# Power.net
KiCad netlist of a schematic drawn in Altium Designer
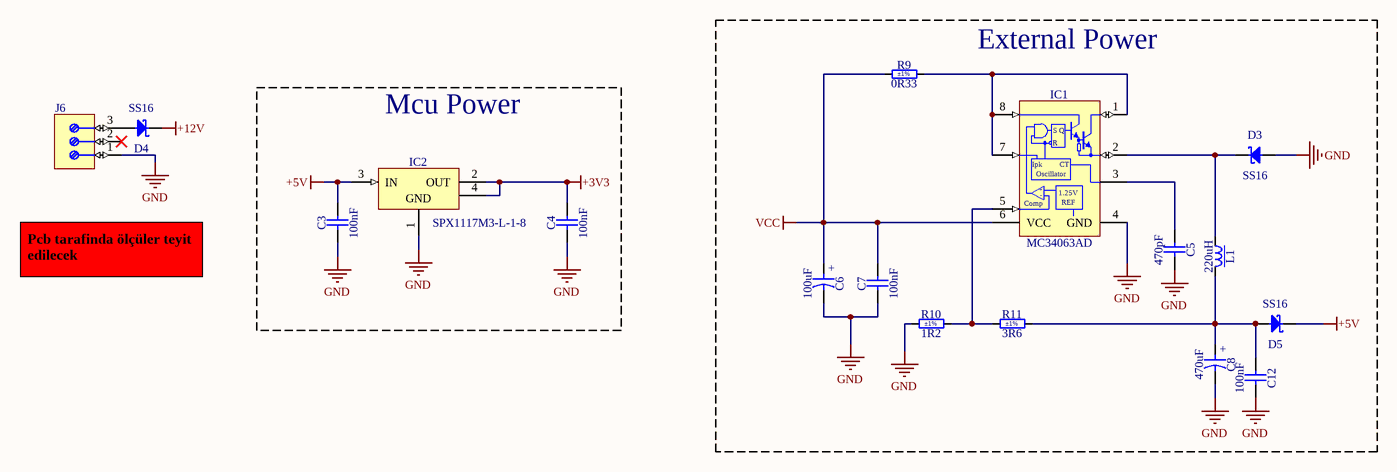
[diagram p0: Power.SchDoc]

(export (version "E")
  (design (tool "Eeschema 10.0.6"))
  (components
    (comp (ref "C3")
      (value "100nF")
      (footprint "CAPC1608X87N")
      (description "Non-polarised capacitor")
      (fields
        (field (name "PART NUMBER") "CC0603_100NF_50V_10%_X5R")
        (field (name "VOLTAGE") "50V")
        (field (name "AUTHOR") "CERN DEM MR")
      )
      (libsource (lib "Capacitors") (part "Capacitor - non polarized"))
    )
    (comp (ref "C4")
      (value "100nF")
      (footprint "CAPC1608X87N")
      (description "Non-polarised capacitor")
      (fields
        (field (name "PART NUMBER") "CC0603_100NF_50V_10%_X5R")
        (field (name "VOLTAGE") "50V")
        (field (name "AUTHOR") "CERN DEM MR")
      )
      (libsource (lib "Capacitors") (part "Capacitor - non polarized"))
    )
    (comp (ref "C5")
      (value "470pF")
      (footprint "CAPC1608X87N")
      (description "Non-polarised capacitor")
      (fields
        (field (name "PART NUMBER") "CC0603_470PF_50V_5%_NP0")
        (field (name "VOLTAGE") "50V")
        (field (name "AUTHOR") "CERN DEM JLC")
      )
      (libsource (lib "Capacitors") (part "Capacitor - non polarized"))
    )
    (comp (ref "C6")
      (value "100uF")
      (footprint "CAPMP7343X200N")
      (description "Polarised capacitor")
      (fields
        (field (name "PART NUMBER") "CTE7343-20_100UF_10V_20%_SANYO_TPC")
        (field (name "VOLTAGE") "10V")
        (field (name "AUTHOR") "CERN DEM JLC")
      )
      (libsource (lib "Capacitors") (part "Capacitor - polarized"))
    )
    (comp (ref "C7")
      (value "100nF")
      (footprint "CAPC1608X87N")
      (description "Non-polarised capacitor")
      (fields
        (field (name "PART NUMBER") "CC0603_100NF_50V_10%_X5R")
        (field (name "VOLTAGE") "50V")
        (field (name "AUTHOR") "CERN DEM MR")
      )
      (libsource (lib "Capacitors") (part "Capacitor - non polarized"))
    )
    (comp (ref "C8")
      (value "470uF")
      (footprint "CAPMP7343X310N")
      (description "Polarised capacitor")
      (fields
        (field (name "PART NUMBER") "CTE7343-31_470UF_6.3V_10%")
        (field (name "VOLTAGE") "6.3V")
        (field (name "AUTHOR") "CERN DEM JLC")
      )
      (libsource (lib "Capacitors") (part "Capacitor - polarized"))
    )
    (comp (ref "C12")
      (value "100nF")
      (footprint "CAPC1608X87N")
      (description "Non-polarised capacitor")
      (fields
        (field (name "PART NUMBER") "CC0603_100NF_50V_10%_X5R")
        (field (name "VOLTAGE") "50V")
        (field (name "AUTHOR") "CERN DEM MR")
      )
      (libsource (lib "Capacitors") (part "Capacitor - non polarized"))
    )
    (comp (ref "D3")
      (value "SS16")
      (footprint "DIOM5127X229N")
      (description "Schottky Diode")
      (fields
        (field (name "VOLTAGE") "60V")
        (field (name "POWER") "1A")
        (field (name "AUTHOR") "CERN DEM JLC")
      )
      (libsource (lib "ICs And Semiconductors") (part "Diode Schottky"))
    )
    (comp (ref "D4")
      (value "SS16")
      (footprint "DIOM5127X229N")
      (description "Schottky Diode")
      (fields
        (field (name "VOLTAGE") "60V")
        (field (name "POWER") "1A")
        (field (name "AUTHOR") "CERN DEM JLC")
      )
      (libsource (lib "ICs And Semiconductors") (part "Diode Schottky"))
    )
    (comp (ref "D5")
      (value "SS16")
      (footprint "DIOM5127X229N")
      (description "Schottky Diode")
      (fields
        (field (name "VOLTAGE") "60V")
        (field (name "POWER") "1A")
        (field (name "AUTHOR") "CERN DEM JLC")
      )
      (libsource (lib "ICs And Semiconductors") (part "Diode Schottky"))
    )
    (comp (ref "IC1")
      (value "MC34063AD")
      (footprint "SOIC127P600X175-8N")
      (description "3V to 40V 1.5A Peak Boost/Buck/Inverting Switching Regulator")
      (fields (field (name "MANUFACTURER") "TEXAS INSTRUMENTS") (field (name "AUTHOR") "CERN DEM JLC"))
      (libsource (lib "ICs And Semiconductors") (part "MC34063A"))
    )
    (comp (ref "IC2")
      (value "SPX1117M3-L-1-8")
      (footprint "SOT230P700X180-4N")
      (description "3-Terminal Regulator 1=GND 2=OUT 3=IN 4=OUT")
      (fields (field (name "MANUFACTURER") "EXAR") (field (name "AUTHOR") "CERN DEM JLC"))
      (libsource (lib "ICs And Semiconductors") (part "REG3+1 1GND-2OUT-3IN+4OUT"))
    )
    (comp (ref "J6")
      (value "~")
      (footprint "PHOENIX_1715734")
      (description "Terminal Block, 3 Positions, Screw Connection")
      (fields
        (field (name "PART NUMBER") "PHOENIX_1715734")
        (field (name "MANUFACTURER") "PHOENIX CONTACT")
        (field (name "AUTHOR") "CERN DEM JLC")
      )
      (libsource (lib "Connectors") (part "Terminal Block_3 Positions_Screw Connection"))
    )
    (comp (ref "L1")
      (value "220uH")
      (footprint "IND_EPCOS_B82464-G4")
      (description "Inductor With Core")
      (fields
        (field (name "PART NUMBER") "IND_470UH_20%_EPCOS_B82464-G4")
        (field (name "POWER") "0.5A")
        (field (name "AUTHOR") "CERN DEM JLC")
      )
      (libsource (lib "Inductors & Transformers") (part "Inductor With Magnetic core"))
    )
    (comp (ref "R9")
      (value "0R33")
      (footprint "RESC3216X65N")
      (description "Resistor - 1%")
      (fields
        (field (name "TOLERANCE") "±1%")
        (field (name "PART NUMBER") "R1206_0R33_1%_0.5W_600PPM")
        (field (name "POWER") "0.5W")
        (field (name "AUTHOR") "CERN DEM JMW")
      )
      (libsource (lib "Resistors") (part "Resistor - 1%"))
    )
    (comp (ref "R10")
      (value "1R2")
      (footprint "RESC1608X55N")
      (description "Resistor - 1%")
      (fields
        (field (name "TOLERANCE") "±1%")
        (field (name "PART NUMBER") "R0603_1R2_1%_0.1W_200PPM")
        (field (name "POWER") "0.1W")
        (field (name "AUTHOR") "CERN DEM JLC")
      )
      (libsource (lib "Resistors") (part "Resistor - 1%"))
    )
    (comp (ref "R11")
      (value "3R6")
      (footprint "RESC1608X55N")
      (description "Resistor - 1%")
      (fields
        (field (name "TOLERANCE") "±1%")
        (field (name "PART NUMBER") "R0603_3R6_1%_0.1W_200PPM")
        (field (name "POWER") "0.1W")
        (field (name "AUTHOR") "CERN DEM JLC")
      )
      (libsource (lib "Resistors") (part "Resistor - 1%"))
    )
  )
  (nets
    (net (code "1") (name "+3V3") (class "Default")
      (node (ref "C4") (pin "2") (pinfunction "2_2") (pintype "passive"))
      (node (ref "IC2") (pin "2") (pinfunction "OUT_2") (pintype "power_in"))
      (node (ref "IC2") (pin "4") (pinfunction "OUT_4") (pintype "power_in"))
    )
    (net (code "2") (name "+5V") (class "Default")
      (node (ref "C3") (pin "2") (pinfunction "2_2") (pintype "passive"))
      (node (ref "D5") (pin "1") (pinfunction "C_1") (pintype "passive"))
      (node (ref "IC2") (pin "3") (pinfunction "IN_3") (pintype "input"))
    )
    (net (code "3") (name "+12V") (class "Default")
      (node (ref "D4") (pin "1") (pinfunction "C_1") (pintype "passive"))
    )
    (net (code "4") (name "GND") (class "Default")
      (node (ref "C12") (pin "2") (pinfunction "2_2") (pintype "passive"))
      (node (ref "C3") (pin "1") (pinfunction "1_1") (pintype "passive"))
      (node (ref "C4") (pin "1") (pinfunction "1_1") (pintype "passive"))
      (node (ref "C5") (pin "2") (pinfunction "2_2") (pintype "passive"))
      (node (ref "C6") (pin "2") (pinfunction "2_2") (pintype "passive"))
      (node (ref "C7") (pin "1") (pinfunction "1_1") (pintype "passive"))
      (node (ref "C8") (pin "2") (pinfunction "2_2") (pintype "passive"))
      (node (ref "D3") (pin "2") (pinfunction "A_2") (pintype "passive"))
      (node (ref "IC1") (pin "4") (pinfunction "GND_4") (pintype "power_in"))
      (node (ref "IC2") (pin "1") (pinfunction "GND_1") (pintype "power_in"))
      (node (ref "J6") (pin "1") (pinfunction "1_1") (pintype "bidirectional"))
      (node (ref "R10") (pin "1") (pinfunction "1_1") (pintype "passive"))
    )
    (net (code "5") (name "Net-(D3-C)") (class "Default")
      (node (ref "D3") (pin "1") (pinfunction "C_1") (pintype "passive"))
      (node (ref "IC1") (pin "2") (pinfunction "SWE_2") (pintype "bidirectional"))
      (node (ref "L1") (pin "1") (pinfunction "1_1") (pintype "passive"))
    )
    (net (code "6") (name "Net-(D4-A)") (class "Default")
      (node (ref "D4") (pin "2") (pinfunction "A_2") (pintype "passive"))
      (node (ref "J6") (pin "3") (pinfunction "3_3") (pintype "bidirectional"))
    )
    (net (code "7") (name "Net-(D5-A)") (class "Default")
      (node (ref "C12") (pin "1") (pinfunction "1_1") (pintype "passive"))
      (node (ref "C8") (pin "1") (pinfunction "1_1") (pintype "passive"))
      (node (ref "D5") (pin "2") (pinfunction "A_2") (pintype "passive"))
      (node (ref "L1") (pin "2") (pinfunction "2_2") (pintype "passive"))
      (node (ref "R11") (pin "2") (pinfunction "2_2") (pintype "passive"))
    )
    (net (code "8") (name "Net-(IC1-COMP)") (class "Default")
      (node (ref "IC1") (pin "5") (pinfunction "COMP_5") (pintype "input"))
      (node (ref "R10") (pin "2") (pinfunction "2_2") (pintype "passive"))
      (node (ref "R11") (pin "1") (pinfunction "1_1") (pintype "passive"))
    )
    (net (code "9") (name "Net-(IC1-DRVC)") (class "Default")
      (node (ref "IC1") (pin "1") (pinfunction "SWC_1") (pintype "bidirectional"))
      (node (ref "IC1") (pin "7") (pinfunction "Ipk_7") (pintype "input"))
      (node (ref "IC1") (pin "8") (pinfunction "DRVC_8") (pintype "input"))
      (node (ref "R9") (pin "2") (pinfunction "2_2") (pintype "passive"))
    )
    (net (code "10") (name "Net-(IC1-TC)") (class "Default")
      (node (ref "C5") (pin "1") (pinfunction "1_1") (pintype "passive"))
      (node (ref "IC1") (pin "3") (pinfunction "TC_3") (pintype "passive"))
    )
    (net (code "11") (name "VCC") (class "Default")
      (node (ref "C6") (pin "1") (pinfunction "1_1") (pintype "passive"))
      (node (ref "C7") (pin "2") (pinfunction "2_2") (pintype "passive"))
      (node (ref "IC1") (pin "6") (pinfunction "VCC_6") (pintype "power_in"))
      (node (ref "R9") (pin "1") (pinfunction "1_1") (pintype "passive"))
    )
    (net (code "12") (name "unconnected-(J6-Pad2)") (class "Default")
      (node (ref "J6") (pin "2") (pinfunction "2_2") (pintype "bidirectional+no_connect"))
    )
  )
)
